# new_wiring.net
KiCad netlist of a schematic drawn in EAGLE
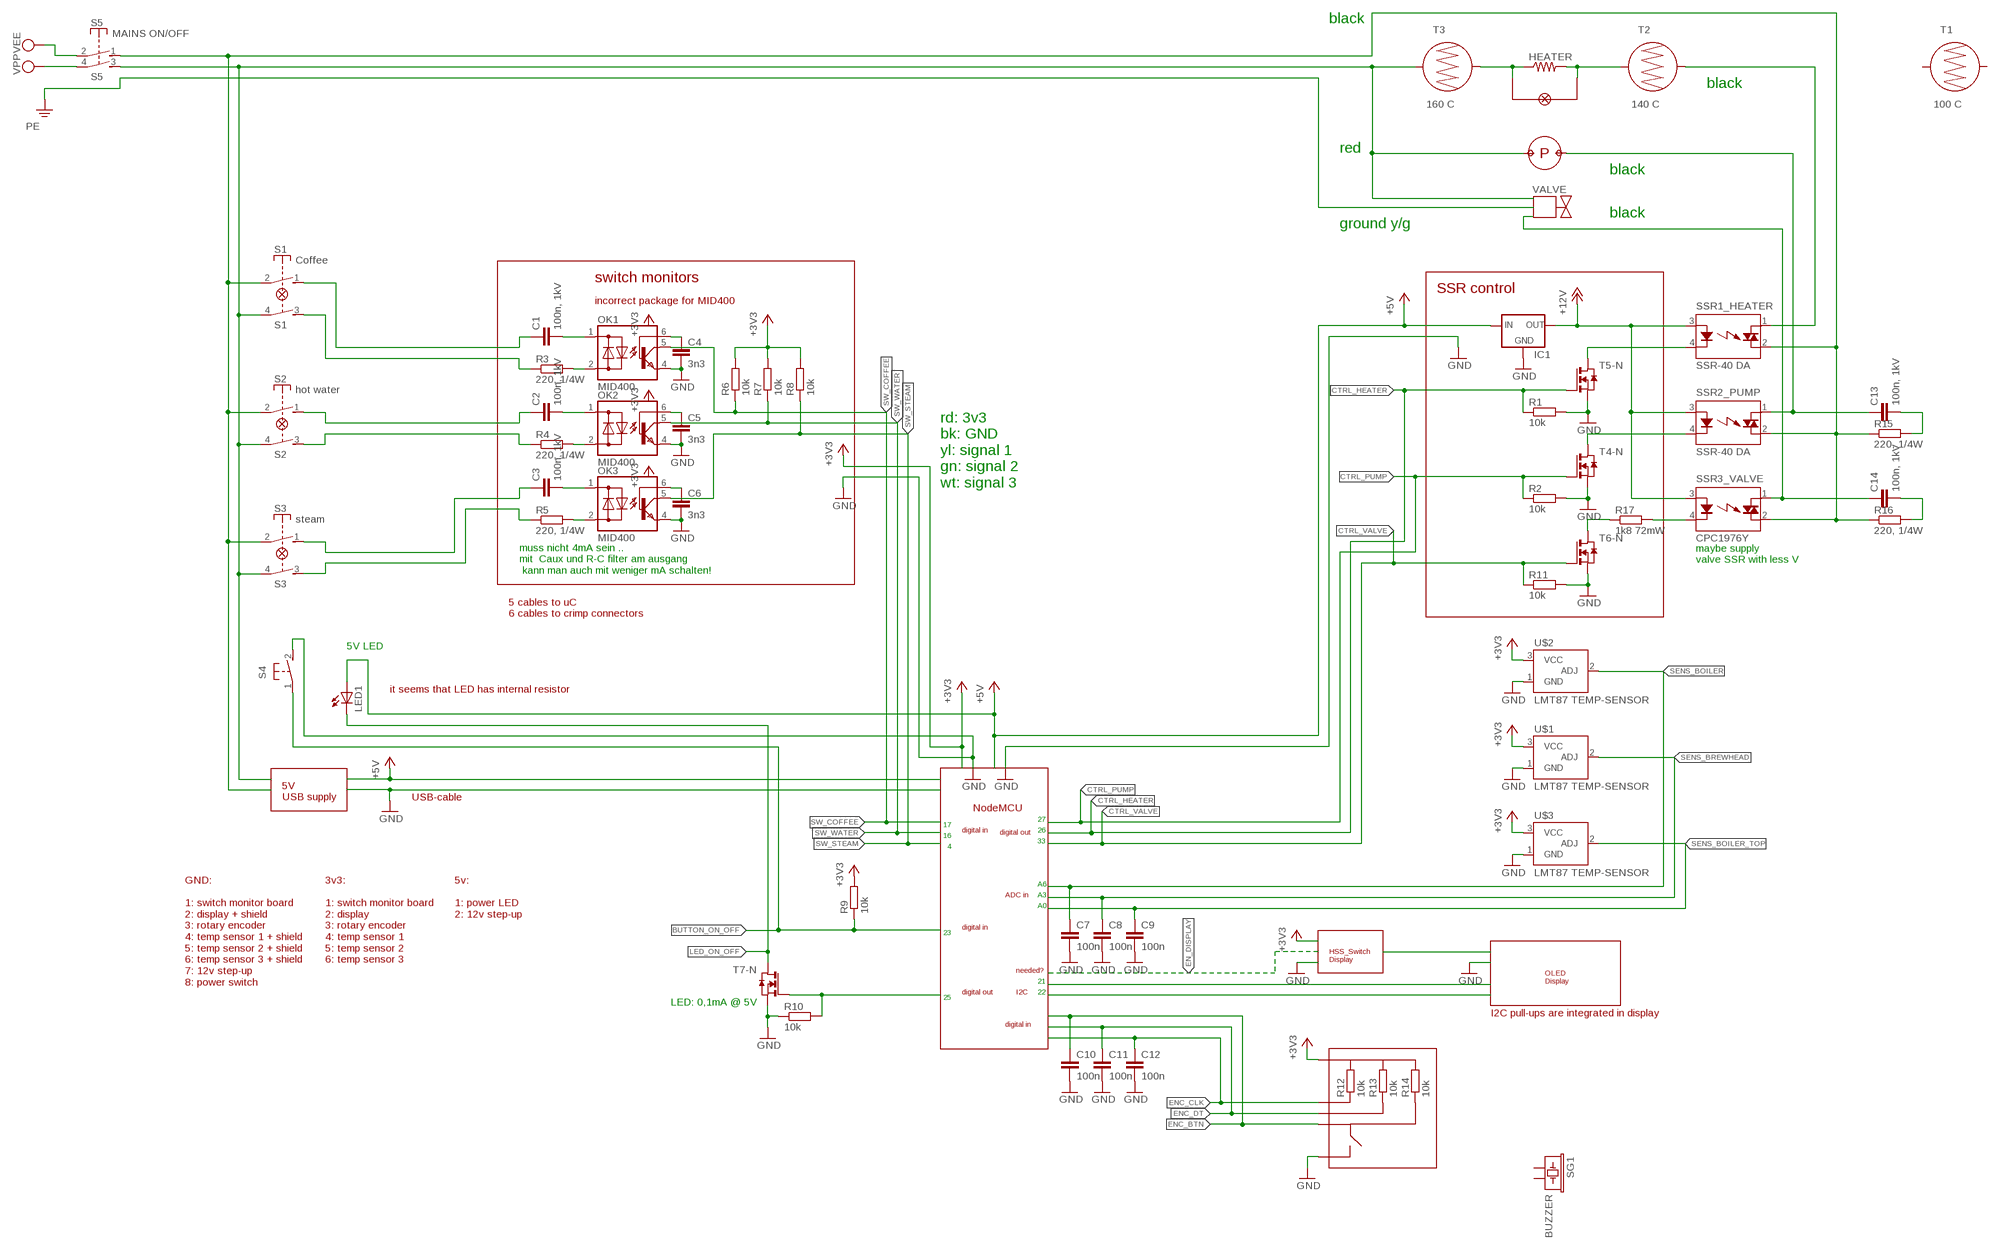
[diagram p0: schematic, sheet 1]

(export (version "E")
  (design (tool "Eeschema 10.0.6"))
  (components
    (comp (ref "C1")
      (value "100n, 1kV")
      (footprint "eagle-import:C025-024X044")
      (libsource (lib "eagle-import") (part "C-EU025-024X044"))
    )
    (comp (ref "C2")
      (value "100n, 1kV")
      (footprint "eagle-import:C025-024X044")
      (libsource (lib "eagle-import") (part "C-EU025-024X044"))
    )
    (comp (ref "C3")
      (value "100n, 1kV")
      (footprint "eagle-import:C025-024X044")
      (libsource (lib "eagle-import") (part "C-EU025-024X044"))
    )
    (comp (ref "C4")
      (value "3n3")
      (footprint "eagle-import:C025-024X044")
      (libsource (lib "eagle-import") (part "C-EU025-024X044"))
    )
    (comp (ref "C5")
      (value "3n3")
      (footprint "eagle-import:C025-024X044")
      (libsource (lib "eagle-import") (part "C-EU025-024X044"))
    )
    (comp (ref "C6")
      (value "3n3")
      (footprint "eagle-import:C025-024X044")
      (libsource (lib "eagle-import") (part "C-EU025-024X044"))
    )
    (comp (ref "C7")
      (value "100n")
      (footprint "eagle-import:C025-024X044")
      (libsource (lib "eagle-import") (part "C-EU025-024X044"))
    )
    (comp (ref "C8")
      (value "100n")
      (footprint "eagle-import:C025-024X044")
      (libsource (lib "eagle-import") (part "C-EU025-024X044"))
    )
    (comp (ref "C9")
      (value "100n")
      (footprint "eagle-import:C025-024X044")
      (libsource (lib "eagle-import") (part "C-EU025-024X044"))
    )
    (comp (ref "C10")
      (value "100n")
      (footprint "eagle-import:C025-024X044")
      (libsource (lib "eagle-import") (part "C-EU025-024X044"))
    )
    (comp (ref "C11")
      (value "100n")
      (footprint "eagle-import:C025-024X044")
      (libsource (lib "eagle-import") (part "C-EU025-024X044"))
    )
    (comp (ref "C12")
      (value "100n")
      (footprint "eagle-import:C025-024X044")
      (libsource (lib "eagle-import") (part "C-EU025-024X044"))
    )
    (comp (ref "C13")
      (value "100n, 1kV")
      (footprint "eagle-import:C025-024X044")
      (libsource (lib "eagle-import") (part "C-EU025-024X044"))
    )
    (comp (ref "C14")
      (value "100n, 1kV")
      (footprint "eagle-import:C025-024X044")
      (libsource (lib "eagle-import") (part "C-EU025-024X044"))
    )
    (comp (ref "FID1")
      (value "FIDUCIAL1.5X3")
      (footprint "eagle-import:FIDUCIAL-1.5X3")
      (libsource (lib "eagle-import") (part "FIDUCIAL1.5X3"))
    )
    (comp (ref "FID2")
      (value "FIDUCIAL1.5X3")
      (footprint "eagle-import:FIDUCIAL-1.5X3")
      (libsource (lib "eagle-import") (part "FIDUCIAL1.5X3"))
    )
    (comp (ref "FID3")
      (value "FIDUCIAL1.5X3")
      (footprint "eagle-import:FIDUCIAL-1.5X3")
      (libsource (lib "eagle-import") (part "FIDUCIAL1.5X3"))
    )
    (comp (ref "FID5")
      (value "FIDUCIAL1.5X3")
      (footprint "eagle-import:FIDUCIAL-1.5X3")
      (libsource (lib "eagle-import") (part "FIDUCIAL1.5X3"))
    )
    (comp (ref "HEATER")
      (value "R-US_VTA52")
      (footprint "eagle-import:VTA52")
      (libsource (lib "eagle-import") (part "R-US_VTA52"))
    )
    (comp (ref "IC1")
      (value "LM123-TO3")
      (footprint "eagle-import:TO3-K02")
      (libsource (lib "eagle-import") (part "LM123-TO3"))
    )
    (comp (ref "LED1")
      (value "LED-3MM-NO_SILK")
      (footprint "eagle-import:LED3MM-NS")
      (libsource (lib "eagle-import") (part "LED-3MM-NO_SILK"))
    )
    (comp (ref "OK1")
      (value "MID400")
      (footprint "eagle-import:DIL06")
      (fields (field (name "MF") "VISHAY/TELEFUNKEN") (field (name "MPN") "IL250"))
      (libsource (lib "eagle-import") (part "IL250"))
    )
    (comp (ref "OK2")
      (value "MID400")
      (footprint "eagle-import:DIL06")
      (fields (field (name "MF") "VISHAY/TELEFUNKEN") (field (name "MPN") "IL250"))
      (libsource (lib "eagle-import") (part "IL250"))
    )
    (comp (ref "OK3")
      (value "MID400")
      (footprint "eagle-import:DIL06")
      (fields (field (name "MF") "VISHAY/TELEFUNKEN") (field (name "MPN") "IL250"))
      (libsource (lib "eagle-import") (part "IL250"))
    )
    (comp (ref "R1")
      (value "10k")
      (footprint "eagle-import:P0613V")
      (libsource (lib "eagle-import") (part "R-EU_0613/5V"))
    )
    (comp (ref "R2")
      (value "10k")
      (footprint "eagle-import:P0613V")
      (libsource (lib "eagle-import") (part "R-EU_0613/5V"))
    )
    (comp (ref "R3")
      (value "220, 1/4W")
      (footprint "eagle-import:P0613V")
      (libsource (lib "eagle-import") (part "R-EU_0613/5V"))
    )
    (comp (ref "R4")
      (value "220, 1/4W")
      (footprint "eagle-import:P0613V")
      (libsource (lib "eagle-import") (part "R-EU_0613/5V"))
    )
    (comp (ref "R5")
      (value "220, 1/4W")
      (footprint "eagle-import:P0613V")
      (libsource (lib "eagle-import") (part "R-EU_0613/5V"))
    )
    (comp (ref "R6")
      (value "10k")
      (footprint "eagle-import:P0613V")
      (libsource (lib "eagle-import") (part "R-EU_0613/5V"))
    )
    (comp (ref "R7")
      (value "10k")
      (footprint "eagle-import:P0613V")
      (libsource (lib "eagle-import") (part "R-EU_0613/5V"))
    )
    (comp (ref "R8")
      (value "10k")
      (footprint "eagle-import:P0613V")
      (libsource (lib "eagle-import") (part "R-EU_0613/5V"))
    )
    (comp (ref "R9")
      (value "10k")
      (footprint "eagle-import:P0613V")
      (libsource (lib "eagle-import") (part "R-EU_0613/5V"))
    )
    (comp (ref "R10")
      (value "10k")
      (footprint "eagle-import:P0613V")
      (libsource (lib "eagle-import") (part "R-EU_0613/5V"))
    )
    (comp (ref "R11")
      (value "10k")
      (footprint "eagle-import:P0613V")
      (libsource (lib "eagle-import") (part "R-EU_0613/5V"))
    )
    (comp (ref "R12")
      (value "10k")
      (footprint "eagle-import:P0613V")
      (libsource (lib "eagle-import") (part "R-EU_0613/5V"))
    )
    (comp (ref "R13")
      (value "10k")
      (footprint "eagle-import:P0613V")
      (libsource (lib "eagle-import") (part "R-EU_0613/5V"))
    )
    (comp (ref "R14")
      (value "10k")
      (footprint "eagle-import:P0613V")
      (libsource (lib "eagle-import") (part "R-EU_0613/5V"))
    )
    (comp (ref "R15")
      (value "220, 1/4W")
      (footprint "eagle-import:P0613V")
      (libsource (lib "eagle-import") (part "R-EU_0613/5V"))
    )
    (comp (ref "R16")
      (value "220, 1/4W")
      (footprint "eagle-import:P0613V")
      (libsource (lib "eagle-import") (part "R-EU_0613/5V"))
    )
    (comp (ref "R17")
      (value "1k8 72mW")
      (footprint "eagle-import:P0613V")
      (libsource (lib "eagle-import") (part "R-EU_0613/5V"))
    )
    (comp (ref "S1")
      (value "Coffee")
      (footprint "eagle-import:PVA1F")
      (libsource (lib "eagle-import") (part "PVA1"))
    )
    (comp (ref "S2")
      (value "hot water")
      (footprint "eagle-import:PVA1F")
      (libsource (lib "eagle-import") (part "PVA1"))
    )
    (comp (ref "S3")
      (value "steam")
      (footprint "eagle-import:PVA1F")
      (libsource (lib "eagle-import") (part "PVA1"))
    )
    (comp (ref "S4")
      (value "31-XX")
      (footprint "eagle-import:B3F-31XX")
      (fields (field (name "MPN") "B3F-3100"))
      (libsource (lib "eagle-import") (part "31-XX"))
    )
    (comp (ref "S5")
      (value "MAINS ON/OFF")
      (footprint "eagle-import:PVA1F")
      (libsource (lib "eagle-import") (part "PVA1"))
    )
    (comp (ref "SG1")
      (value "BUZZER")
      (footprint "eagle-import:BUZZER-12MM-NS")
      (libsource (lib "eagle-import") (part "BUZZERNS"))
    )
    (comp (ref "SSR1_HEATER")
      (value "SSR-40 DA")
      (footprint "eagle-import:S102T0X")
      (libsource (lib "eagle-import") (part "S?101T01"))
    )
    (comp (ref "SSR2_PUMP")
      (value "SSR-40 DA")
      (footprint "eagle-import:S102T0X")
      (libsource (lib "eagle-import") (part "S?101T01"))
    )
    (comp (ref "SSR3_VALVE")
      (value "CPC1976Y")
      (footprint "eagle-import:S102T0X")
      (libsource (lib "eagle-import") (part "S?101T01"))
    )
    (comp (ref "T1")
      (value "100 C")
      (footprint "eagle-import:BUTTON-CONDUCTIVE")
      (libsource (lib "eagle-import") (part "BUTTON-CONDUCTIVESMD"))
    )
    (comp (ref "T2")
      (value "140 C")
      (footprint "eagle-import:BUTTON-CONDUCTIVE")
      (libsource (lib "eagle-import") (part "BUTTON-CONDUCTIVESMD"))
    )
    (comp (ref "T3")
      (value "160 C")
      (footprint "eagle-import:BUTTON-CONDUCTIVE")
      (libsource (lib "eagle-import") (part "BUTTON-CONDUCTIVESMD"))
    )
    (comp (ref "T4")
      (value "N/P-MOS-DMG1029SV")
      (footprint "eagle-import:SOT-563")
      (libsource (lib "eagle-import") (part "N/P-MOS-DMG1029SV"))
    )
    (comp (ref "T5")
      (value "N/P-MOS-DMG1029SV")
      (footprint "eagle-import:SOT-563")
      (libsource (lib "eagle-import") (part "N/P-MOS-DMG1029SV"))
    )
    (comp (ref "T6")
      (value "N/P-MOS-DMG1029SV")
      (footprint "eagle-import:SOT-563")
      (libsource (lib "eagle-import") (part "N/P-MOS-DMG1029SV"))
    )
    (comp (ref "T7")
      (value "N/P-MOS-DMG1029SV")
      (footprint "eagle-import:SOT-563")
      (libsource (lib "eagle-import") (part "N/P-MOS-DMG1029SV"))
    )
    (comp (ref "TP1")
      (value "TPB1,27")
      (footprint "eagle-import:B1,27")
      (libsource (lib "eagle-import") (part "TPB1,27"))
    )
    (comp (ref "TP2")
      (value "TPB1,27")
      (footprint "eagle-import:B1,27")
      (libsource (lib "eagle-import") (part "TPB1,27"))
    )
    (comp (ref "U$1")
      (value "LMT87 TEMP-SENSOR")
      (footprint "eagle-import:TO-92")
      (libsource (lib "eagle-import") (part "TEMPERATURE-SENSOR"))
    )
    (comp (ref "U$2")
      (value "LMT87 TEMP-SENSOR")
      (footprint "eagle-import:TO-92")
      (libsource (lib "eagle-import") (part "TEMPERATURE-SENSOR"))
    )
    (comp (ref "U$3")
      (value "LMT87 TEMP-SENSOR")
      (footprint "eagle-import:TO-92")
      (libsource (lib "eagle-import") (part "TEMPERATURE-SENSOR"))
    )
  )
  (nets
    (net (code "1") (name "+3V3") (class "Default")
      (node (ref "R6") (pin "2") (pinfunction "2_2") (pintype "passive"))
      (node (ref "R7") (pin "2") (pinfunction "2_2") (pintype "passive"))
      (node (ref "R8") (pin "2") (pinfunction "2_2") (pintype "passive"))
      (node (ref "R9") (pin "2") (pinfunction "2_2") (pintype "passive"))
      (node (ref "U$1") (pin "3") (pinfunction "VCC_3") (pintype "bidirectional"))
      (node (ref "U$2") (pin "3") (pinfunction "VCC_3") (pintype "bidirectional"))
      (node (ref "U$3") (pin "3") (pinfunction "VCC_3") (pintype "bidirectional"))
    )
    (net (code "2") (name "+5V") (class "Default")
      (node (ref "IC1") (pin "2") (pinfunction "IN_2") (pintype "input"))
      (node (ref "LED1") (pin "A") (pinfunction "A_A") (pintype "passive"))
    )
    (net (code "3") (name "+12V") (class "Default")
      (node (ref "IC1") (pin "1") (pinfunction "OUT_1") (pintype "passive"))
      (node (ref "SSR1_HEATER") (pin "3") (pinfunction "A_3") (pintype "passive"))
      (node (ref "SSR2_PUMP") (pin "3") (pinfunction "A_3") (pintype "passive"))
      (node (ref "SSR3_VALVE") (pin "3") (pinfunction "A_3") (pintype "passive"))
    )
    (net (code "4") (name "BUTTON_ON_OFF") (class "Default")
      (node (ref "R9") (pin "1") (pinfunction "1_1") (pintype "passive"))
      (node (ref "S4") (pin "1") (pinfunction "P_1") (pintype "passive"))
    )
    (net (code "5") (name "CTRL_HEATER") (class "Default")
      (node (ref "R1") (pin "1") (pinfunction "1_1") (pintype "passive"))
      (node (ref "T5") (pin "2") (pinfunction "G_2") (pintype "passive"))
    )
    (net (code "6") (name "CTRL_PUMP") (class "Default")
      (node (ref "R2") (pin "1") (pinfunction "1_1") (pintype "passive"))
      (node (ref "T4") (pin "2") (pinfunction "G_2") (pintype "passive"))
    )
    (net (code "7") (name "CTRL_VALVE") (class "Default")
      (node (ref "R11") (pin "1") (pinfunction "1_1") (pintype "passive"))
      (node (ref "T6") (pin "2") (pinfunction "G_2") (pintype "passive"))
    )
    (net (code "8") (name "ENC_BTN") (class "Default")
      (node (ref "C10") (pin "1") (pinfunction "1_1") (pintype "passive"))
    )
    (net (code "9") (name "ENC_CLK") (class "Default")
      (node (ref "C12") (pin "1") (pinfunction "1_1") (pintype "passive"))
    )
    (net (code "10") (name "ENC_DT") (class "Default")
      (node (ref "C11") (pin "1") (pinfunction "1_1") (pintype "passive"))
    )
    (net (code "12") (name "GND") (class "Default")
      (node (ref "C10") (pin "2") (pinfunction "2_2") (pintype "passive"))
      (node (ref "C11") (pin "2") (pinfunction "2_2") (pintype "passive"))
      (node (ref "C12") (pin "2") (pinfunction "2_2") (pintype "passive"))
      (node (ref "C4") (pin "2") (pinfunction "2_2") (pintype "passive"))
      (node (ref "C5") (pin "2") (pinfunction "2_2") (pintype "passive"))
      (node (ref "C6") (pin "2") (pinfunction "2_2") (pintype "passive"))
      (node (ref "C7") (pin "2") (pinfunction "2_2") (pintype "passive"))
      (node (ref "C8") (pin "2") (pinfunction "2_2") (pintype "passive"))
      (node (ref "C9") (pin "2") (pinfunction "2_2") (pintype "passive"))
      (node (ref "IC1") (pin "3") (pinfunction "GND_3") (pintype "input"))
      (node (ref "OK1") (pin "4") (pinfunction "E_4") (pintype "passive"))
      (node (ref "OK2") (pin "4") (pinfunction "E_4") (pintype "passive"))
      (node (ref "OK3") (pin "4") (pinfunction "E_4") (pintype "passive"))
      (node (ref "R1") (pin "2") (pinfunction "2_2") (pintype "passive"))
      (node (ref "R10") (pin "1") (pinfunction "1_1") (pintype "passive"))
      (node (ref "R11") (pin "2") (pinfunction "2_2") (pintype "passive"))
      (node (ref "R2") (pin "2") (pinfunction "2_2") (pintype "passive"))
      (node (ref "S4") (pin "2") (pinfunction "S_2") (pintype "passive"))
      (node (ref "T4") (pin "1") (pinfunction "S_1") (pintype "passive"))
      (node (ref "T5") (pin "1") (pinfunction "S_1") (pintype "passive"))
      (node (ref "T6") (pin "1") (pinfunction "S_1") (pintype "passive"))
      (node (ref "T7") (pin "1") (pinfunction "S_1") (pintype "passive"))
      (node (ref "U$1") (pin "1") (pinfunction "GND_1") (pintype "bidirectional"))
      (node (ref "U$2") (pin "1") (pinfunction "GND_1") (pintype "bidirectional"))
      (node (ref "U$3") (pin "1") (pinfunction "GND_1") (pintype "bidirectional"))
    )
    (net (code "13") (name "LED_ON_OFF") (class "Default")
      (node (ref "LED1") (pin "K") (pinfunction "C_K") (pintype "passive"))
      (node (ref "T7") (pin "6") (pinfunction "D_6") (pintype "passive"))
    )
    (net (code "14") (name "Net-(C13-Pad2)") (class "Default")
      (node (ref "C13") (pin "2") (pinfunction "2_2") (pintype "passive"))
      (node (ref "R15") (pin "2") (pinfunction "2_2") (pintype "passive"))
    )
    (net (code "15") (name "Net-(C14-Pad2)") (class "Default")
      (node (ref "C14") (pin "2") (pinfunction "2_2") (pintype "passive"))
      (node (ref "R16") (pin "2") (pinfunction "2_2") (pintype "passive"))
    )
    (net (code "16") (name "Net-(HEATER-Pad1)") (class "Default")
      (node (ref "HEATER") (pin "1") (pinfunction "1_1") (pintype "passive"))
      (node (ref "T3") (pin "2") (pinfunction "2_2") (pintype "passive"))
    )
    (net (code "17") (name "Net-(HEATER-Pad2)") (class "Default")
      (node (ref "HEATER") (pin "2") (pinfunction "2_2") (pintype "passive"))
      (node (ref "T2") (pin "1") (pinfunction "1_1") (pintype "passive"))
    )
    (net (code "18") (name "Net-(OK1-AC1)") (class "Default")
      (node (ref "C1") (pin "2") (pinfunction "2_2") (pintype "passive"))
      (node (ref "OK1") (pin "1") (pinfunction "AC1_1") (pintype "passive"))
    )
    (net (code "19") (name "Net-(OK1-AC2)") (class "Default")
      (node (ref "OK1") (pin "2") (pinfunction "AC2_2") (pintype "passive"))
      (node (ref "R3") (pin "2") (pinfunction "2_2") (pintype "passive"))
    )
    (net (code "20") (name "Net-(OK1-B)") (class "Default")
      (node (ref "C4") (pin "1") (pinfunction "1_1") (pintype "passive"))
      (node (ref "OK1") (pin "6") (pinfunction "B_6") (pintype "passive"))
    )
    (net (code "21") (name "Net-(OK2-AC1)") (class "Default")
      (node (ref "C2") (pin "2") (pinfunction "2_2") (pintype "passive"))
      (node (ref "OK2") (pin "1") (pinfunction "AC1_1") (pintype "passive"))
    )
    (net (code "22") (name "Net-(OK2-AC2)") (class "Default")
      (node (ref "OK2") (pin "2") (pinfunction "AC2_2") (pintype "passive"))
      (node (ref "R4") (pin "2") (pinfunction "2_2") (pintype "passive"))
    )
    (net (code "23") (name "Net-(OK2-B)") (class "Default")
      (node (ref "C5") (pin "1") (pinfunction "1_1") (pintype "passive"))
      (node (ref "OK2") (pin "6") (pinfunction "B_6") (pintype "passive"))
    )
    (net (code "24") (name "Net-(OK3-AC1)") (class "Default")
      (node (ref "C3") (pin "2") (pinfunction "2_2") (pintype "passive"))
      (node (ref "OK3") (pin "1") (pinfunction "AC1_1") (pintype "passive"))
    )
    (net (code "25") (name "Net-(OK3-AC2)") (class "Default")
      (node (ref "OK3") (pin "2") (pinfunction "AC2_2") (pintype "passive"))
      (node (ref "R5") (pin "2") (pinfunction "2_2") (pintype "passive"))
    )
    (net (code "26") (name "Net-(OK3-B)") (class "Default")
      (node (ref "C6") (pin "1") (pinfunction "1_1") (pintype "passive"))
      (node (ref "OK3") (pin "6") (pinfunction "B_6") (pintype "passive"))
    )
    (net (code "27") (name "Net-(S1A-P)") (class "Default")
      (node (ref "R15") (pin "1") (pinfunction "1_1") (pintype "passive"))
      (node (ref "R16") (pin "1") (pinfunction "1_1") (pintype "passive"))
      (node (ref "S1") (pin "2") (pinfunction "P_2") (pintype "passive"))
      (node (ref "S2") (pin "2") (pinfunction "P_2") (pintype "passive"))
      (node (ref "S3") (pin "2") (pinfunction "P_2") (pintype "passive"))
      (node (ref "S5") (pin "1") (pinfunction "S_1") (pintype "passive"))
      (node (ref "SSR1_HEATER") (pin "2") (pinfunction "DS2_2") (pintype "passive"))
      (node (ref "SSR2_PUMP") (pin "2") (pinfunction "DS2_2") (pintype "passive"))
      (node (ref "SSR3_VALVE") (pin "2") (pinfunction "DS2_2") (pintype "passive"))
    )
    (net (code "28") (name "Net-(S1A-S)") (class "Default")
      (node (ref "C1") (pin "1") (pinfunction "1_1") (pintype "passive"))
      (node (ref "S1") (pin "1") (pinfunction "S_1") (pintype "passive"))
    )
    (net (code "29") (name "Net-(S1B-P)") (class "Default")
      (node (ref "S1") (pin "4") (pinfunction "P_4") (pintype "passive"))
      (node (ref "S2") (pin "4") (pinfunction "P_4") (pintype "passive"))
      (node (ref "S3") (pin "4") (pinfunction "P_4") (pintype "passive"))
      (node (ref "S5") (pin "3") (pinfunction "S_3") (pintype "passive"))
      (node (ref "T3") (pin "1") (pinfunction "1_1") (pintype "passive"))
      (node (ref "TP2") (pin "TP") (pinfunction "TP_TP") (pintype "input"))
    )
    (net (code "30") (name "Net-(S1B-S)") (class "Default")
      (node (ref "R3") (pin "1") (pinfunction "1_1") (pintype "passive"))
      (node (ref "S1") (pin "3") (pinfunction "S_3") (pintype "passive"))
    )
    (net (code "31") (name "Net-(S2A-S)") (class "Default")
      (node (ref "C2") (pin "1") (pinfunction "1_1") (pintype "passive"))
      (node (ref "S2") (pin "1") (pinfunction "S_1") (pintype "passive"))
    )
    (net (code "32") (name "Net-(S2B-S)") (class "Default")
      (node (ref "R4") (pin "1") (pinfunction "1_1") (pintype "passive"))
      (node (ref "S2") (pin "3") (pinfunction "S_3") (pintype "passive"))
    )
    (net (code "33") (name "Net-(S3A-S)") (class "Default")
      (node (ref "C3") (pin "1") (pinfunction "1_1") (pintype "passive"))
      (node (ref "S3") (pin "1") (pinfunction "S_1") (pintype "passive"))
    )
    (net (code "34") (name "Net-(S3B-S)") (class "Default")
      (node (ref "R5") (pin "1") (pinfunction "1_1") (pintype "passive"))
      (node (ref "S3") (pin "3") (pinfunction "S_3") (pintype "passive"))
    )
    (net (code "35") (name "Net-(SSR1_HEATER-DS1)") (class "Default")
      (node (ref "SSR1_HEATER") (pin "1") (pinfunction "DS1_1") (pintype "passive"))
      (node (ref "T2") (pin "2") (pinfunction "2_2") (pintype "passive"))
    )
    (net (code "36") (name "Net-(SSR1_HEATER-K)") (class "Default")
      (node (ref "SSR1_HEATER") (pin "4") (pinfunction "K_4") (pintype "passive"))
      (node (ref "T5") (pin "6") (pinfunction "D_6") (pintype "passive"))
    )
    (net (code "37") (name "Net-(SSR2_PUMP-DS1)") (class "Default")
      (node (ref "C13") (pin "1") (pinfunction "1_1") (pintype "passive"))
      (node (ref "SSR2_PUMP") (pin "1") (pinfunction "DS1_1") (pintype "passive"))
      (node (ref "TP1") (pin "TP") (pinfunction "TP_TP") (pintype "input"))
    )
    (net (code "38") (name "Net-(SSR2_PUMP-K)") (class "Default")
      (node (ref "SSR2_PUMP") (pin "4") (pinfunction "K_4") (pintype "passive"))
      (node (ref "T4") (pin "6") (pinfunction "D_6") (pintype "passive"))
    )
    (net (code "39") (name "Net-(SSR3_VALVE-DS1)") (class "Default")
      (node (ref "C14") (pin "1") (pinfunction "1_1") (pintype "passive"))
      (node (ref "SSR3_VALVE") (pin "1") (pinfunction "DS1_1") (pintype "passive"))
    )
    (net (code "40") (name "Net-(SSR3_VALVE-K)") (class "Default")
      (node (ref "R17") (pin "2") (pinfunction "2_2") (pintype "passive"))
      (node (ref "SSR3_VALVE") (pin "4") (pinfunction "K_4") (pintype "passive"))
    )
    (net (code "41") (name "Net-(T6A-D)") (class "Default")
      (node (ref "R17") (pin "1") (pinfunction "1_1") (pintype "passive"))
      (node (ref "T6") (pin "6") (pinfunction "D_6") (pintype "passive"))
    )
    (net (code "42") (name "Net-(T7A-G)") (class "Default")
      (node (ref "R10") (pin "2") (pinfunction "2_2") (pintype "passive"))
      (node (ref "T7") (pin "2") (pinfunction "G_2") (pintype "passive"))
    )
    (net (code "44") (name "SENS_BOILER") (class "Default")
      (node (ref "C7") (pin "1") (pinfunction "1_1") (pintype "passive"))
      (node (ref "U$2") (pin "2") (pinfunction "ADJ_2") (pintype "bidirectional"))
    )
    (net (code "45") (name "SENS_BOILER_TOP") (class "Default")
      (node (ref "C9") (pin "1") (pinfunction "1_1") (pintype "passive"))
      (node (ref "U$3") (pin "2") (pinfunction "ADJ_2") (pintype "bidirectional"))
    )
    (net (code "46") (name "SENS_BREWHEAD") (class "Default")
      (node (ref "C8") (pin "1") (pinfunction "1_1") (pintype "passive"))
      (node (ref "U$1") (pin "2") (pinfunction "ADJ_2") (pintype "bidirectional"))
    )
    (net (code "47") (name "SW_COFFEE") (class "Default")
      (node (ref "OK1") (pin "5") (pinfunction "C_5") (pintype "passive"))
      (node (ref "R6") (pin "1") (pinfunction "1_1") (pintype "passive"))
    )
    (net (code "48") (name "SW_STEAM") (class "Default")
      (node (ref "OK3") (pin "5") (pinfunction "C_5") (pintype "passive"))
      (node (ref "R8") (pin "1") (pinfunction "1_1") (pintype "passive"))
    )
    (net (code "49") (name "SW_WATER") (class "Default")
      (node (ref "OK2") (pin "5") (pinfunction "C_5") (pintype "passive"))
      (node (ref "R7") (pin "1") (pinfunction "1_1") (pintype "passive"))
    )
    (net (code "50") (name "VEE") (class "Default")
      (node (ref "S5") (pin "2") (pinfunction "P_2") (pintype "passive"))
    )
    (net (code "51") (name "VPP") (class "Default")
      (node (ref "S5") (pin "4") (pinfunction "P_4") (pintype "passive"))
    )
    (net (code "52") (name "unconnected-(R12-Pad1)") (class "Default")
      (node (ref "R12") (pin "1") (pinfunction "1_1") (pintype "passive"))
    )
    (net (code "53") (name "unconnected-(R12-Pad2)") (class "Default")
      (node (ref "R12") (pin "2") (pinfunction "2_2") (pintype "passive"))
    )
    (net (code "54") (name "unconnected-(R13-Pad1)") (class "Default")
      (node (ref "R13") (pin "1") (pinfunction "1_1") (pintype "passive"))
    )
    (net (code "55") (name "unconnected-(R13-Pad2)") (class "Default")
      (node (ref "R13") (pin "2") (pinfunction "2_2") (pintype "passive"))
    )
    (net (code "56") (name "unconnected-(R14-Pad1)") (class "Default")
      (node (ref "R14") (pin "1") (pinfunction "1_1") (pintype "passive"))
    )
    (net (code "57") (name "unconnected-(R14-Pad2)") (class "Default")
      (node (ref "R14") (pin "2") (pinfunction "2_2") (pintype "passive"))
    )
    (net (code "58") (name "unconnected-(SG1-1-Pad+)") (class "Default")
      (node (ref "SG1") (pin "+") (pinfunction "1_+") (pintype "passive"))
    )
    (net (code "59") (name "unconnected-(SG1-2-Pad-)") (class "Default")
      (node (ref "SG1") (pin "-") (pinfunction "2_-") (pintype "passive"))
    )
    (net (code "60") (name "unconnected-(T1-Pad1)") (class "Default")
      (node (ref "T1") (pin "1") (pinfunction "1_1") (pintype "passive"))
    )
    (net (code "61") (name "unconnected-(T1-Pad2)") (class "Default")
      (node (ref "T1") (pin "2") (pinfunction "2_2") (pintype "passive"))
    )
  )
)
